# SheetMain.net
KiCad netlist of a schematic drawn in Altium Designer
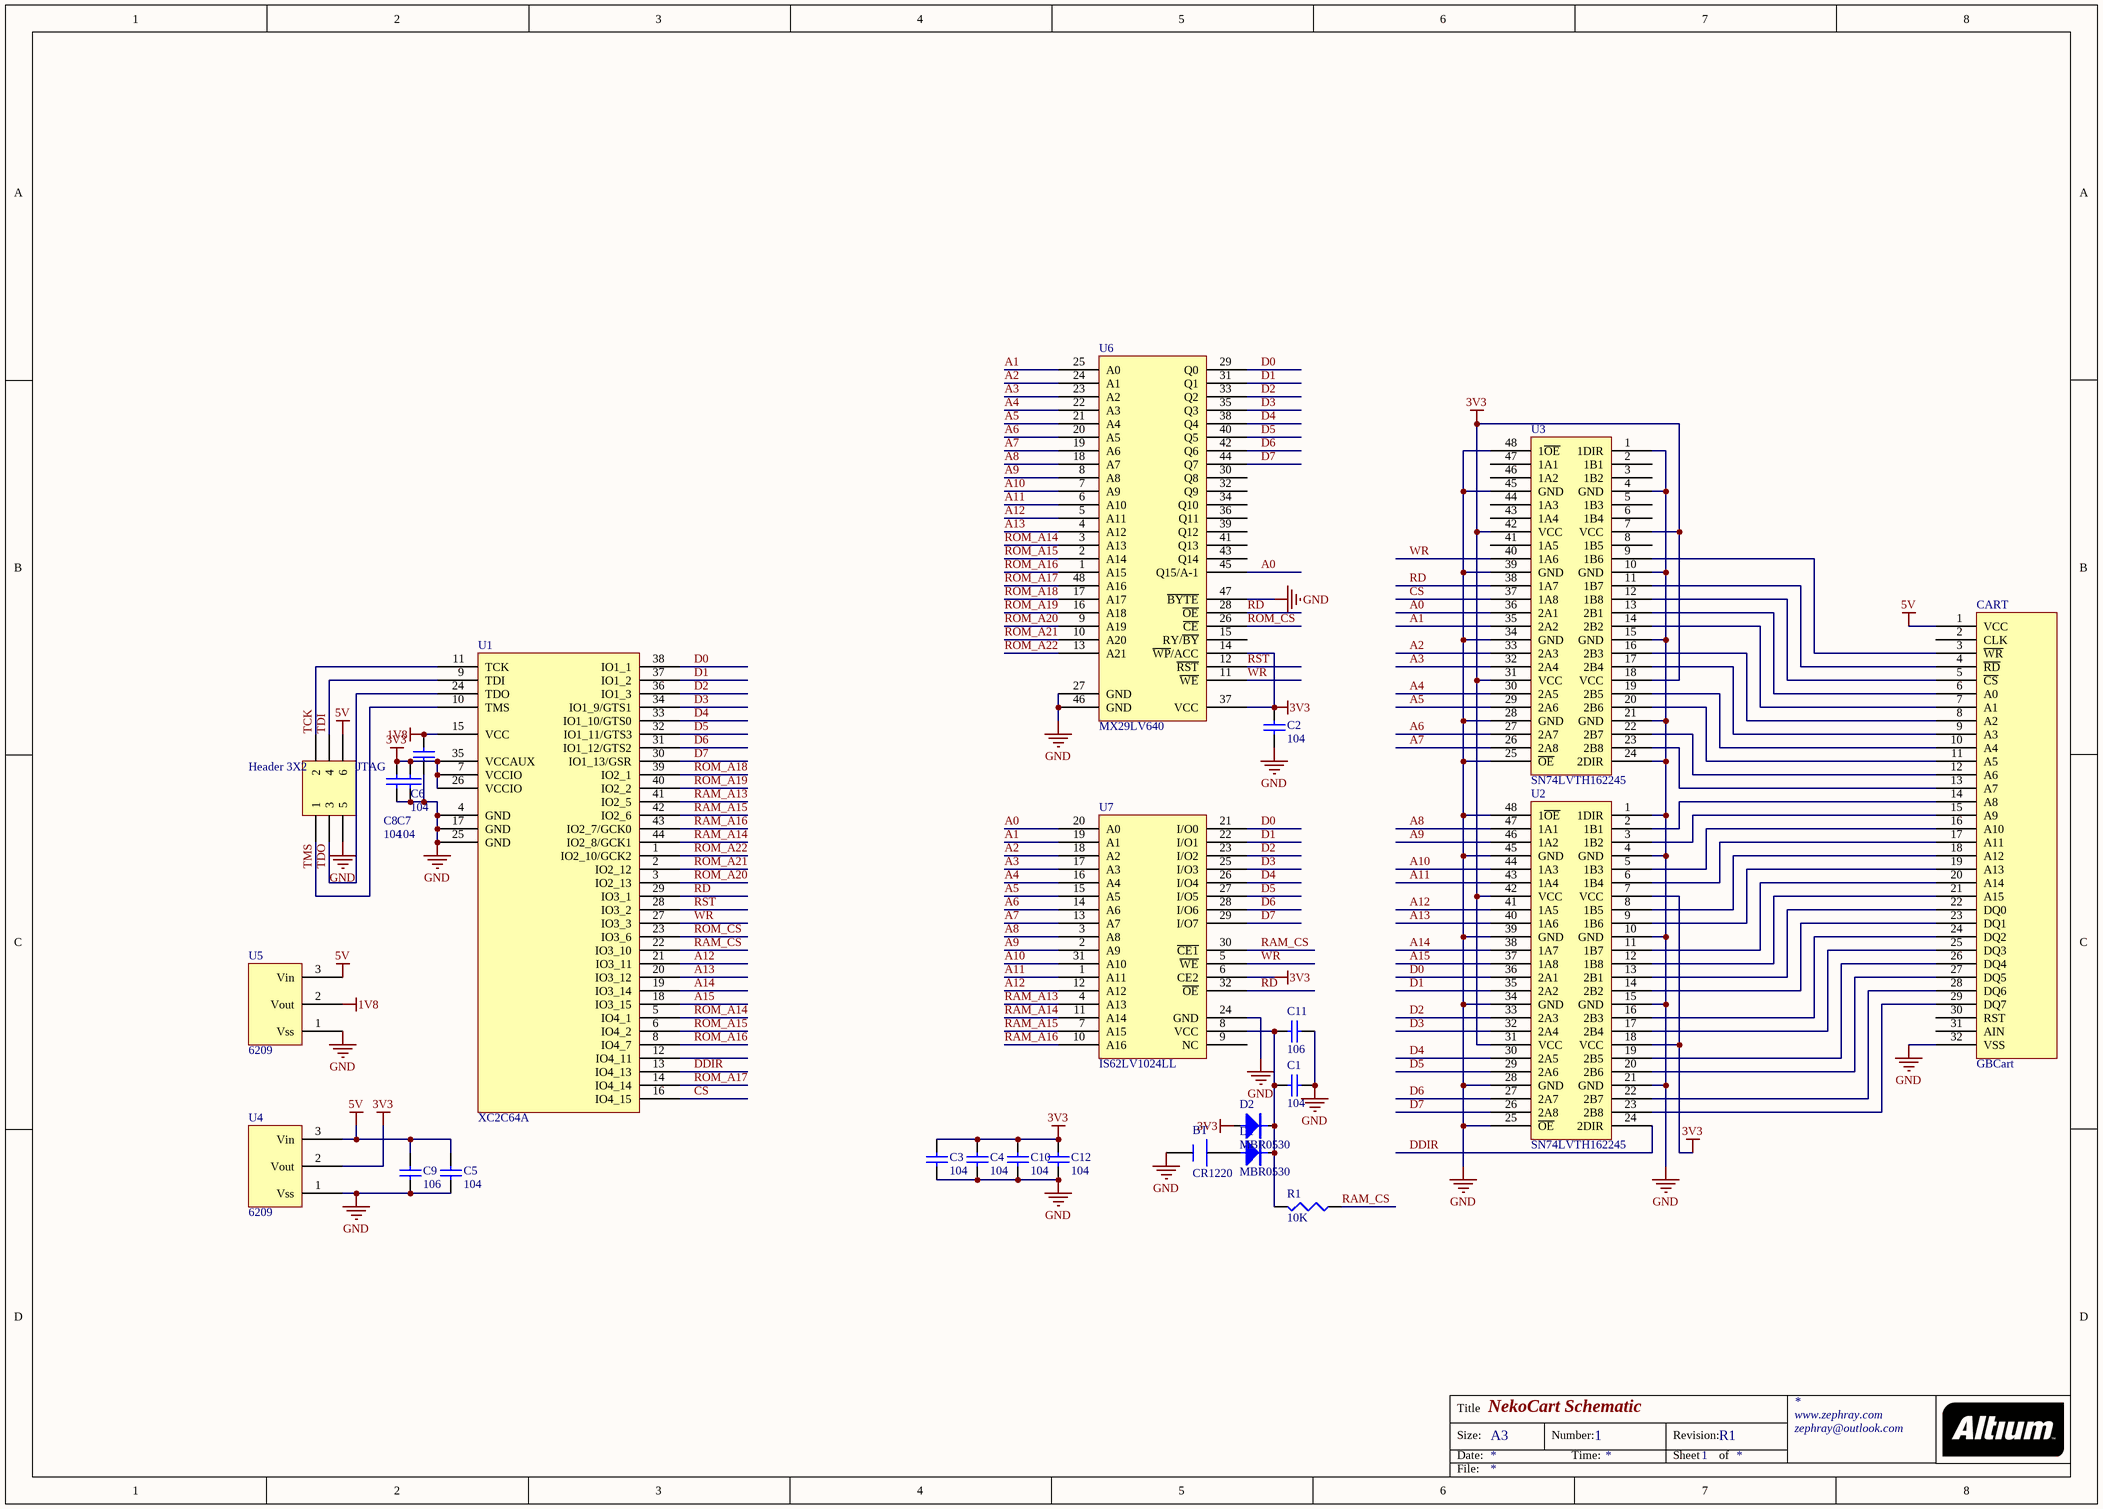
[diagram p0: SheetMain.SchDoc]

(export (version "E")
  (design (tool "Eeschema 10.0.6"))
  (components
    (comp (ref "BT")
      (value "CR1220")
      (footprint "CR1220")
      (fields (field (name "PUBLISHER") "Altium Limited"))
      (libsource (lib "Schlib1") (part "CR1220"))
    )
    (comp (ref "C1")
      (value "104")
      (footprint "1608[0603]")
      (description "Capacitor (Semiconductor SIM Model)")
      (fields (field (name "PUBLISHER") "Altium Limited"))
      (libsource (lib "Miscellaneous Devices") (part "Cap Semi"))
    )
    (comp (ref "C2")
      (value "104")
      (footprint "1608[0603]")
      (description "Capacitor (Semiconductor SIM Model)")
      (fields (field (name "PUBLISHER") "Altium Limited"))
      (libsource (lib "Miscellaneous Devices") (part "Cap Semi"))
    )
    (comp (ref "C3")
      (value "104")
      (footprint "1608[0603]")
      (description "Capacitor (Semiconductor SIM Model)")
      (fields (field (name "PUBLISHER") "Altium Limited"))
      (libsource (lib "Miscellaneous Devices") (part "Cap Semi"))
    )
    (comp (ref "C4")
      (value "104")
      (footprint "1608[0603]")
      (description "Capacitor (Semiconductor SIM Model)")
      (fields (field (name "PUBLISHER") "Altium Limited"))
      (libsource (lib "Miscellaneous Devices") (part "Cap Semi"))
    )
    (comp (ref "C5")
      (value "104")
      (footprint "1608[0603]")
      (description "Capacitor (Semiconductor SIM Model)")
      (fields (field (name "PUBLISHER") "Altium Limited"))
      (libsource (lib "Miscellaneous Devices") (part "Cap Semi"))
    )
    (comp (ref "C6")
      (value "104")
      (footprint "1608[0603]")
      (description "Capacitor (Semiconductor SIM Model)")
      (fields (field (name "PUBLISHER") "Altium Limited"))
      (libsource (lib "Miscellaneous Devices") (part "Cap Semi"))
    )
    (comp (ref "C7")
      (value "104")
      (footprint "1608[0603]")
      (description "Capacitor (Semiconductor SIM Model)")
      (fields (field (name "PUBLISHER") "Altium Limited"))
      (libsource (lib "Miscellaneous Devices") (part "Cap Semi"))
    )
    (comp (ref "C8")
      (value "104")
      (footprint "1608[0603]")
      (description "Capacitor (Semiconductor SIM Model)")
      (fields (field (name "PUBLISHER") "Altium Limited"))
      (libsource (lib "Miscellaneous Devices") (part "Cap Semi"))
    )
    (comp (ref "C9")
      (value "106")
      (footprint "C0805")
      (description "Capacitor (Semiconductor SIM Model)")
      (fields (field (name "PUBLISHER") "Altium Limited"))
      (libsource (lib "Miscellaneous Devices") (part "Cap Semi"))
    )
    (comp (ref "C10")
      (value "104")
      (footprint "1608[0603]")
      (description "Capacitor (Semiconductor SIM Model)")
      (fields (field (name "PUBLISHER") "Altium Limited"))
      (libsource (lib "Miscellaneous Devices") (part "Cap Semi"))
    )
    (comp (ref "C11")
      (value "106")
      (footprint "C0805")
      (description "Capacitor (Semiconductor SIM Model)")
      (fields (field (name "PUBLISHER") "Altium Limited"))
      (libsource (lib "Miscellaneous Devices") (part "Cap Semi"))
    )
    (comp (ref "C12")
      (value "104")
      (footprint "1608[0603]")
      (description "Capacitor (Semiconductor SIM Model)")
      (fields (field (name "PUBLISHER") "Altium Limited"))
      (libsource (lib "Miscellaneous Devices") (part "Cap Semi"))
    )
    (comp (ref "CART") (value "GBCart") (footprint "GB_CART") (libsource (lib "Schlib1") (part "GBCart")))
    (comp (ref "D1") (value "MBR0530") (footprint "0805D") (libsource (lib "Schlib1") (part "1N4148")))
    (comp (ref "D2") (value "MBR0530") (footprint "0805D") (libsource (lib "Schlib1") (part "1N4148")))
    (comp (ref "JTAG")
      (value "Header 3X2")
      (footprint "HDR2X3")
      (description "Header, 3-Pin, Dual row")
      (fields (field (name "PUBLISHER") "Altium Limited"))
      (libsource (lib "Miscellaneous Connectors") (part "Header 3X2"))
    )
    (comp (ref "R1")
      (value "10K")
      (footprint "J1-0603")
      (description "Resistor")
      (fields (field (name "PUBLISHER") "Altium Limited"))
      (libsource (lib "Miscellaneous Devices") (part "Res3"))
    )
    (comp (ref "U1") (value "XC2C64A") (footprint "44A_L") (libsource (lib "Schlib1") (part "XC2C64A")))
    (comp (ref "U2")
      (value "SN74LVTH162245")
      (footprint "TSOP48")
      (libsource (lib "Schlib1") (part "SN74LVTH162245"))
    )
    (comp (ref "U3")
      (value "SN74LVTH162245")
      (footprint "TSOP48")
      (libsource (lib "Schlib1") (part "SN74LVTH162245"))
    )
    (comp (ref "U4") (value "6209") (footprint "SOT-23") (libsource (lib "Schlib1") (part "6209")))
    (comp (ref "U5") (value "6209") (footprint "SOT-23") (libsource (lib "Schlib1") (part "6209")))
    (comp (ref "U6") (value "MX29LV640") (footprint "TSOP48L") (libsource (lib "Schlib1") (part "MX29LV640")))
    (comp (ref "U7")
      (value "IS62LV1024LL")
      (footprint "TSOP32")
      (libsource (lib "Schlib1") (part "IS62LV1024LL"))
    )
  )
  (nets
    (net (code "1") (name "/A0") (class "Default")
      (node (ref "U3") (pin "36") (pinfunction "2A1_36") (pintype "passive"))
      (node (ref "U6") (pin "45") (pinfunction "Q15/A-1_45") (pintype "passive"))
      (node (ref "U7") (pin "20") (pinfunction "A0_20") (pintype "passive"))
    )
    (net (code "2") (name "/A1") (class "Default")
      (node (ref "U3") (pin "35") (pinfunction "2A2_35") (pintype "passive"))
      (node (ref "U6") (pin "25") (pinfunction "A0_25") (pintype "passive"))
      (node (ref "U7") (pin "19") (pinfunction "A1_19") (pintype "passive"))
    )
    (net (code "3") (name "/A2") (class "Default")
      (node (ref "U3") (pin "33") (pinfunction "2A3_33") (pintype "passive"))
      (node (ref "U6") (pin "24") (pinfunction "A1_24") (pintype "passive"))
      (node (ref "U7") (pin "18") (pinfunction "A2_18") (pintype "passive"))
    )
    (net (code "4") (name "/A3") (class "Default")
      (node (ref "U3") (pin "32") (pinfunction "2A4_32") (pintype "passive"))
      (node (ref "U6") (pin "23") (pinfunction "A2_23") (pintype "passive"))
      (node (ref "U7") (pin "17") (pinfunction "A3_17") (pintype "passive"))
    )
    (net (code "5") (name "/A4") (class "Default")
      (node (ref "U3") (pin "30") (pinfunction "2A5_30") (pintype "passive"))
      (node (ref "U6") (pin "22") (pinfunction "A3_22") (pintype "passive"))
      (node (ref "U7") (pin "16") (pinfunction "A4_16") (pintype "passive"))
    )
    (net (code "6") (name "/A5") (class "Default")
      (node (ref "U3") (pin "29") (pinfunction "2A6_29") (pintype "passive"))
      (node (ref "U6") (pin "21") (pinfunction "A4_21") (pintype "passive"))
      (node (ref "U7") (pin "15") (pinfunction "A5_15") (pintype "passive"))
    )
    (net (code "7") (name "/A6") (class "Default")
      (node (ref "U3") (pin "27") (pinfunction "2A7_27") (pintype "passive"))
      (node (ref "U6") (pin "20") (pinfunction "A5_20") (pintype "passive"))
      (node (ref "U7") (pin "14") (pinfunction "A6_14") (pintype "passive"))
    )
    (net (code "8") (name "/A7") (class "Default")
      (node (ref "U3") (pin "26") (pinfunction "2A8_26") (pintype "passive"))
      (node (ref "U6") (pin "19") (pinfunction "A6_19") (pintype "passive"))
      (node (ref "U7") (pin "13") (pinfunction "A7_13") (pintype "passive"))
    )
    (net (code "9") (name "/A8") (class "Default")
      (node (ref "U2") (pin "47") (pinfunction "1A1_47") (pintype "passive"))
      (node (ref "U6") (pin "18") (pinfunction "A7_18") (pintype "passive"))
      (node (ref "U7") (pin "3") (pinfunction "A8_3") (pintype "passive"))
    )
    (net (code "10") (name "/A9") (class "Default")
      (node (ref "U2") (pin "46") (pinfunction "1A2_46") (pintype "passive"))
      (node (ref "U6") (pin "8") (pinfunction "A8_8") (pintype "passive"))
      (node (ref "U7") (pin "2") (pinfunction "A9_2") (pintype "passive"))
    )
    (net (code "11") (name "/A10") (class "Default")
      (node (ref "U2") (pin "44") (pinfunction "1A3_44") (pintype "passive"))
      (node (ref "U6") (pin "7") (pinfunction "A9_7") (pintype "passive"))
      (node (ref "U7") (pin "31") (pinfunction "A10_31") (pintype "passive"))
    )
    (net (code "12") (name "/A11") (class "Default")
      (node (ref "U2") (pin "43") (pinfunction "1A4_43") (pintype "passive"))
      (node (ref "U6") (pin "6") (pinfunction "A10_6") (pintype "passive"))
      (node (ref "U7") (pin "1") (pinfunction "A11_1") (pintype "passive"))
    )
    (net (code "13") (name "/A12") (class "Default")
      (node (ref "U1") (pin "21") (pinfunction "IO3_11_21") (pintype "passive"))
      (node (ref "U2") (pin "41") (pinfunction "1A5_41") (pintype "passive"))
      (node (ref "U6") (pin "5") (pinfunction "A11_5") (pintype "passive"))
      (node (ref "U7") (pin "12") (pinfunction "A12_12") (pintype "passive"))
    )
    (net (code "14") (name "/A13") (class "Default")
      (node (ref "U1") (pin "20") (pinfunction "IO3_12_20") (pintype "passive"))
      (node (ref "U2") (pin "40") (pinfunction "1A6_40") (pintype "passive"))
      (node (ref "U6") (pin "4") (pinfunction "A12_4") (pintype "passive"))
    )
    (net (code "15") (name "/A14") (class "Default")
      (node (ref "U1") (pin "19") (pinfunction "IO3_14_19") (pintype "passive"))
      (node (ref "U2") (pin "38") (pinfunction "1A7_38") (pintype "passive"))
    )
    (net (code "16") (name "/A15") (class "Default")
      (node (ref "U1") (pin "18") (pinfunction "IO3_15_18") (pintype "passive"))
      (node (ref "U2") (pin "37") (pinfunction "1A8_37") (pintype "passive"))
    )
    (net (code "17") (name "/CS") (class "Default")
      (node (ref "U1") (pin "16") (pinfunction "IO4_15_16") (pintype "passive"))
      (node (ref "U3") (pin "37") (pinfunction "1A8_37") (pintype "passive"))
    )
    (net (code "18") (name "/D0") (class "Default")
      (node (ref "U1") (pin "38") (pinfunction "IO1_1_38") (pintype "passive"))
      (node (ref "U2") (pin "36") (pinfunction "2A1_36") (pintype "passive"))
      (node (ref "U6") (pin "29") (pinfunction "Q0_29") (pintype "passive"))
      (node (ref "U7") (pin "21") (pinfunction "I/O0_21") (pintype "passive"))
    )
    (net (code "19") (name "/D1") (class "Default")
      (node (ref "U1") (pin "37") (pinfunction "IO1_2_37") (pintype "passive"))
      (node (ref "U2") (pin "35") (pinfunction "2A2_35") (pintype "passive"))
      (node (ref "U6") (pin "31") (pinfunction "Q1_31") (pintype "passive"))
      (node (ref "U7") (pin "22") (pinfunction "I/O1_22") (pintype "passive"))
    )
    (net (code "20") (name "/D2") (class "Default")
      (node (ref "U1") (pin "36") (pinfunction "IO1_3_36") (pintype "passive"))
      (node (ref "U2") (pin "33") (pinfunction "2A3_33") (pintype "passive"))
      (node (ref "U6") (pin "33") (pinfunction "Q2_33") (pintype "passive"))
      (node (ref "U7") (pin "23") (pinfunction "I/O2_23") (pintype "passive"))
    )
    (net (code "21") (name "/D3") (class "Default")
      (node (ref "U1") (pin "34") (pinfunction "IO1_9/GTS1_34") (pintype "passive"))
      (node (ref "U2") (pin "32") (pinfunction "2A4_32") (pintype "passive"))
      (node (ref "U6") (pin "35") (pinfunction "Q3_35") (pintype "passive"))
      (node (ref "U7") (pin "25") (pinfunction "I/O3_25") (pintype "passive"))
    )
    (net (code "22") (name "/D4") (class "Default")
      (node (ref "U1") (pin "33") (pinfunction "IO1_10/GTS0_33") (pintype "passive"))
      (node (ref "U2") (pin "30") (pinfunction "2A5_30") (pintype "passive"))
      (node (ref "U6") (pin "38") (pinfunction "Q4_38") (pintype "passive"))
      (node (ref "U7") (pin "26") (pinfunction "I/O4_26") (pintype "passive"))
    )
    (net (code "23") (name "/D5") (class "Default")
      (node (ref "U1") (pin "32") (pinfunction "IO1_11/GTS3_32") (pintype "passive"))
      (node (ref "U2") (pin "29") (pinfunction "2A6_29") (pintype "passive"))
      (node (ref "U6") (pin "40") (pinfunction "Q5_40") (pintype "passive"))
      (node (ref "U7") (pin "27") (pinfunction "I/O5_27") (pintype "passive"))
    )
    (net (code "24") (name "/D6") (class "Default")
      (node (ref "U1") (pin "31") (pinfunction "IO1_12/GTS2_31") (pintype "passive"))
      (node (ref "U2") (pin "27") (pinfunction "2A7_27") (pintype "passive"))
      (node (ref "U6") (pin "42") (pinfunction "Q6_42") (pintype "passive"))
      (node (ref "U7") (pin "28") (pinfunction "I/O6_28") (pintype "passive"))
    )
    (net (code "25") (name "/D7") (class "Default")
      (node (ref "U1") (pin "30") (pinfunction "IO1_13/GSR_30") (pintype "passive"))
      (node (ref "U2") (pin "26") (pinfunction "2A8_26") (pintype "passive"))
      (node (ref "U6") (pin "44") (pinfunction "Q7_44") (pintype "passive"))
      (node (ref "U7") (pin "29") (pinfunction "I/O7_29") (pintype "passive"))
    )
    (net (code "26") (name "/DDIR") (class "Default")
      (node (ref "U1") (pin "13") (pinfunction "IO4_13_13") (pintype "passive"))
      (node (ref "U2") (pin "24") (pinfunction "2DIR_24") (pintype "passive"))
    )
    (net (code "27") (name "/RAM_A13") (class "Default")
      (node (ref "U1") (pin "41") (pinfunction "IO2_5_41") (pintype "passive"))
      (node (ref "U7") (pin "4") (pinfunction "A13_4") (pintype "passive"))
    )
    (net (code "28") (name "/RAM_A14") (class "Default")
      (node (ref "U1") (pin "44") (pinfunction "IO2_8/GCK1_44") (pintype "passive"))
      (node (ref "U7") (pin "11") (pinfunction "A14_11") (pintype "passive"))
    )
    (net (code "29") (name "/RAM_A15") (class "Default")
      (node (ref "U1") (pin "42") (pinfunction "IO2_6_42") (pintype "passive"))
      (node (ref "U7") (pin "7") (pinfunction "A15_7") (pintype "passive"))
    )
    (net (code "30") (name "/RAM_A16") (class "Default")
      (node (ref "U1") (pin "43") (pinfunction "IO2_7/GCK0_43") (pintype "passive"))
      (node (ref "U7") (pin "10") (pinfunction "A16_10") (pintype "passive"))
    )
    (net (code "31") (name "/RAM_CS") (class "Default")
      (node (ref "R1") (pin "1") (pinfunction "1_1") (pintype "passive"))
      (node (ref "U1") (pin "22") (pinfunction "IO3_10_22") (pintype "passive"))
      (node (ref "U7") (pin "30") (pinfunction "~{CE1}_30") (pintype "passive"))
    )
    (net (code "32") (name "/RD") (class "Default")
      (node (ref "U1") (pin "29") (pinfunction "IO3_1_29") (pintype "passive"))
      (node (ref "U3") (pin "38") (pinfunction "1A7_38") (pintype "passive"))
      (node (ref "U6") (pin "28") (pinfunction "~{OE}_28") (pintype "passive"))
      (node (ref "U7") (pin "32") (pinfunction "~{OE}_32") (pintype "passive"))
    )
    (net (code "33") (name "/ROM_A14") (class "Default")
      (node (ref "U1") (pin "5") (pinfunction "IO4_1_5") (pintype "passive"))
      (node (ref "U6") (pin "3") (pinfunction "A13_3") (pintype "passive"))
    )
    (net (code "34") (name "/ROM_A15") (class "Default")
      (node (ref "U1") (pin "6") (pinfunction "IO4_2_6") (pintype "passive"))
      (node (ref "U6") (pin "2") (pinfunction "A14_2") (pintype "passive"))
    )
    (net (code "35") (name "/ROM_A16") (class "Default")
      (node (ref "U1") (pin "8") (pinfunction "IO4_7_8") (pintype "passive"))
      (node (ref "U6") (pin "1") (pinfunction "A15_1") (pintype "passive"))
    )
    (net (code "36") (name "/ROM_A17") (class "Default")
      (node (ref "U1") (pin "14") (pinfunction "IO4_14_14") (pintype "passive"))
      (node (ref "U6") (pin "48") (pinfunction "A16_48") (pintype "passive"))
    )
    (net (code "37") (name "/ROM_A18") (class "Default")
      (node (ref "U1") (pin "39") (pinfunction "IO2_1_39") (pintype "passive"))
      (node (ref "U6") (pin "17") (pinfunction "A17_17") (pintype "passive"))
    )
    (net (code "38") (name "/ROM_A19") (class "Default")
      (node (ref "U1") (pin "40") (pinfunction "IO2_2_40") (pintype "passive"))
      (node (ref "U6") (pin "16") (pinfunction "A18_16") (pintype "passive"))
    )
    (net (code "39") (name "/ROM_A20") (class "Default")
      (node (ref "U1") (pin "3") (pinfunction "IO2_13_3") (pintype "passive"))
      (node (ref "U6") (pin "9") (pinfunction "A19_9") (pintype "passive"))
    )
    (net (code "40") (name "/ROM_A21") (class "Default")
      (node (ref "U1") (pin "2") (pinfunction "IO2_12_2") (pintype "passive"))
      (node (ref "U6") (pin "10") (pinfunction "A20_10") (pintype "passive"))
    )
    (net (code "41") (name "/ROM_A22") (class "Default")
      (node (ref "U1") (pin "1") (pinfunction "IO2_10/GCK2_1") (pintype "passive"))
      (node (ref "U6") (pin "13") (pinfunction "A21_13") (pintype "passive"))
    )
    (net (code "42") (name "/ROM_CS") (class "Default")
      (node (ref "U1") (pin "23") (pinfunction "IO3_6_23") (pintype "passive"))
      (node (ref "U6") (pin "26") (pinfunction "~{CE}_26") (pintype "passive"))
    )
    (net (code "43") (name "/RST") (class "Default")
      (node (ref "U1") (pin "28") (pinfunction "IO3_2_28") (pintype "passive"))
      (node (ref "U6") (pin "12") (pinfunction "~{RST}_12") (pintype "passive"))
    )
    (net (code "44") (name "/TCK") (class "Default")
      (node (ref "JTAG") (pin "2") (pinfunction "2_2") (pintype "passive"))
      (node (ref "U1") (pin "11") (pinfunction "TCK_11") (pintype "passive"))
    )
    (net (code "45") (name "/TDI") (class "Default")
      (node (ref "JTAG") (pin "4") (pinfunction "4_4") (pintype "passive"))
      (node (ref "U1") (pin "9") (pinfunction "TDI_9") (pintype "passive"))
    )
    (net (code "46") (name "/TDO") (class "Default")
      (node (ref "JTAG") (pin "3") (pinfunction "3_3") (pintype "passive"))
      (node (ref "U1") (pin "24") (pinfunction "TDO_24") (pintype "passive"))
    )
    (net (code "47") (name "/TMS") (class "Default")
      (node (ref "JTAG") (pin "1") (pinfunction "1_1") (pintype "passive"))
      (node (ref "U1") (pin "10") (pinfunction "TMS_10") (pintype "passive"))
    )
    (net (code "48") (name "/WR") (class "Default")
      (node (ref "U1") (pin "27") (pinfunction "IO3_3_27") (pintype "passive"))
      (node (ref "U3") (pin "40") (pinfunction "1A6_40") (pintype "passive"))
      (node (ref "U6") (pin "11") (pinfunction "~{WE}_11") (pintype "passive"))
      (node (ref "U7") (pin "5") (pinfunction "~{WE}_5") (pintype "passive"))
    )
    (net (code "49") (name "1V8") (class "Default")
      (node (ref "C6") (pin "2") (pinfunction "2_2") (pintype "passive"))
      (node (ref "U1") (pin "15") (pinfunction "VCC_15") (pintype "passive"))
      (node (ref "U5") (pin "2") (pinfunction "Vout_2") (pintype "passive"))
    )
    (net (code "50") (name "3V3") (class "Default")
      (node (ref "C10") (pin "1") (pinfunction "1_1") (pintype "passive"))
      (node (ref "C12") (pin "2") (pinfunction "2_2") (pintype "passive"))
      (node (ref "C2") (pin "2") (pinfunction "2_2") (pintype "passive"))
      (node (ref "C3") (pin "2") (pinfunction "2_2") (pintype "passive"))
      (node (ref "C4") (pin "2") (pinfunction "2_2") (pintype "passive"))
      (node (ref "C7") (pin "2") (pinfunction "2_2") (pintype "passive"))
      (node (ref "C8") (pin "2") (pinfunction "2_2") (pintype "passive"))
      (node (ref "D2") (pin "A") (pinfunction "1_A") (pintype "passive"))
      (node (ref "U1") (pin "26") (pinfunction "VCCIO_26") (pintype "passive"))
      (node (ref "U1") (pin "35") (pinfunction "VCCAUX_35") (pintype "passive"))
      (node (ref "U1") (pin "7") (pinfunction "VCCIO_7") (pintype "passive"))
      (node (ref "U2") (pin "18") (pinfunction "VCC_18") (pintype "passive"))
      (node (ref "U2") (pin "31") (pinfunction "VCC_31") (pintype "passive"))
      (node (ref "U2") (pin "42") (pinfunction "VCC_42") (pintype "passive"))
      (node (ref "U2") (pin "7") (pinfunction "VCC_7") (pintype "passive"))
      (node (ref "U3") (pin "18") (pinfunction "VCC_18") (pintype "passive"))
      (node (ref "U3") (pin "31") (pinfunction "VCC_31") (pintype "passive"))
      (node (ref "U3") (pin "42") (pinfunction "VCC_42") (pintype "passive"))
      (node (ref "U3") (pin "7") (pinfunction "VCC_7") (pintype "passive"))
      (node (ref "U4") (pin "2") (pinfunction "Vout_2") (pintype "passive"))
      (node (ref "U6") (pin "14") (pinfunction "~{WP}/ACC_14") (pintype "passive"))
      (node (ref "U6") (pin "37") (pinfunction "VCC_37") (pintype "passive"))
      (node (ref "U7") (pin "6") (pinfunction "CE2_6") (pintype "passive"))
    )
    (net (code "51") (name "5V") (class "Default")
      (node (ref "C5") (pin "2") (pinfunction "2_2") (pintype "passive"))
      (node (ref "C9") (pin "2") (pinfunction "2_2") (pintype "passive"))
      (node (ref "CART") (pin "1") (pinfunction "VCC_1") (pintype "passive"))
      (node (ref "JTAG") (pin "6") (pinfunction "6_6") (pintype "passive"))
      (node (ref "U4") (pin "3") (pinfunction "Vin_3") (pintype "passive"))
      (node (ref "U5") (pin "3") (pinfunction "Vin_3") (pintype "passive"))
    )
    (net (code "52") (name "GND") (class "Default")
      (node (ref "BT") (pin "2") (pinfunction "-_2") (pintype "passive"))
      (node (ref "C1") (pin "1") (pinfunction "1_1") (pintype "passive"))
      (node (ref "C10") (pin "2") (pinfunction "2_2") (pintype "passive"))
      (node (ref "C11") (pin "1") (pinfunction "1_1") (pintype "passive"))
      (node (ref "C12") (pin "1") (pinfunction "1_1") (pintype "passive"))
      (node (ref "C2") (pin "1") (pinfunction "1_1") (pintype "passive"))
      (node (ref "C3") (pin "1") (pinfunction "1_1") (pintype "passive"))
      (node (ref "C4") (pin "1") (pinfunction "1_1") (pintype "passive"))
      (node (ref "C5") (pin "1") (pinfunction "1_1") (pintype "passive"))
      (node (ref "C6") (pin "1") (pinfunction "1_1") (pintype "passive"))
      (node (ref "C7") (pin "1") (pinfunction "1_1") (pintype "passive"))
      (node (ref "C8") (pin "1") (pinfunction "1_1") (pintype "passive"))
      (node (ref "C9") (pin "1") (pinfunction "1_1") (pintype "passive"))
      (node (ref "CART") (pin "32") (pinfunction "VSS_32") (pintype "passive"))
      (node (ref "JTAG") (pin "5") (pinfunction "5_5") (pintype "passive"))
      (node (ref "U1") (pin "17") (pinfunction "GND_17") (pintype "passive"))
      (node (ref "U1") (pin "25") (pinfunction "GND_25") (pintype "passive"))
      (node (ref "U1") (pin "4") (pinfunction "GND_4") (pintype "passive"))
      (node (ref "U2") (pin "1") (pinfunction "1DIR_1") (pintype "passive"))
      (node (ref "U2") (pin "10") (pinfunction "GND_10") (pintype "passive"))
      (node (ref "U2") (pin "15") (pinfunction "GND_15") (pintype "passive"))
      (node (ref "U2") (pin "21") (pinfunction "GND_21") (pintype "passive"))
      (node (ref "U2") (pin "25") (pinfunction "~{OE}_25") (pintype "passive"))
      (node (ref "U2") (pin "28") (pinfunction "GND_28") (pintype "passive"))
      (node (ref "U2") (pin "34") (pinfunction "GND_34") (pintype "passive"))
      (node (ref "U2") (pin "39") (pinfunction "GND_39") (pintype "passive"))
      (node (ref "U2") (pin "4") (pinfunction "GND_4") (pintype "passive"))
      (node (ref "U2") (pin "45") (pinfunction "GND_45") (pintype "passive"))
      (node (ref "U2") (pin "48") (pinfunction "1~{OE}_48") (pintype "passive"))
      (node (ref "U3") (pin "1") (pinfunction "1DIR_1") (pintype "passive"))
      (node (ref "U3") (pin "10") (pinfunction "GND_10") (pintype "passive"))
      (node (ref "U3") (pin "15") (pinfunction "GND_15") (pintype "passive"))
      (node (ref "U3") (pin "21") (pinfunction "GND_21") (pintype "passive"))
      (node (ref "U3") (pin "24") (pinfunction "2DIR_24") (pintype "passive"))
      (node (ref "U3") (pin "25") (pinfunction "~{OE}_25") (pintype "passive"))
      (node (ref "U3") (pin "28") (pinfunction "GND_28") (pintype "passive"))
      (node (ref "U3") (pin "34") (pinfunction "GND_34") (pintype "passive"))
      (node (ref "U3") (pin "39") (pinfunction "GND_39") (pintype "passive"))
      (node (ref "U3") (pin "4") (pinfunction "GND_4") (pintype "passive"))
      (node (ref "U3") (pin "45") (pinfunction "GND_45") (pintype "passive"))
      (node (ref "U3") (pin "48") (pinfunction "1~{OE}_48") (pintype "passive"))
      (node (ref "U4") (pin "1") (pinfunction "Vss_1") (pintype "passive"))
      (node (ref "U5") (pin "1") (pinfunction "Vss_1") (pintype "passive"))
      (node (ref "U6") (pin "27") (pinfunction "GND_27") (pintype "passive"))
      (node (ref "U6") (pin "46") (pinfunction "GND_46") (pintype "passive"))
      (node (ref "U6") (pin "47") (pinfunction "~{BYTE}_47") (pintype "passive"))
      (node (ref "U7") (pin "24") (pinfunction "GND_24") (pintype "passive"))
    )
    (net (code "53") (name "Net-(BT-+)") (class "Default")
      (node (ref "BT") (pin "1") (pinfunction "+_1") (pintype "passive"))
      (node (ref "D1") (pin "A") (pinfunction "1_A") (pintype "passive"))
    )
    (net (code "54") (name "Net-(CART-A0)") (class "Default")
      (node (ref "CART") (pin "6") (pinfunction "A0_6") (pintype "passive"))
      (node (ref "U3") (pin "13") (pinfunction "2B1_13") (pintype "passive"))
    )
    (net (code "55") (name "Net-(CART-A1)") (class "Default")
      (node (ref "CART") (pin "7") (pinfunction "A1_7") (pintype "passive"))
      (node (ref "U3") (pin "14") (pinfunction "2B2_14") (pintype "passive"))
    )
    (net (code "56") (name "Net-(CART-A2)") (class "Default")
      (node (ref "CART") (pin "8") (pinfunction "A2_8") (pintype "passive"))
      (node (ref "U3") (pin "16") (pinfunction "2B3_16") (pintype "passive"))
    )
    (net (code "57") (name "Net-(CART-A3)") (class "Default")
      (node (ref "CART") (pin "9") (pinfunction "A3_9") (pintype "passive"))
      (node (ref "U3") (pin "17") (pinfunction "2B4_17") (pintype "passive"))
    )
    (net (code "58") (name "Net-(CART-A4)") (class "Default")
      (node (ref "CART") (pin "10") (pinfunction "A4_10") (pintype "passive"))
      (node (ref "U3") (pin "19") (pinfunction "2B5_19") (pintype "passive"))
    )
    (net (code "59") (name "Net-(CART-A5)") (class "Default")
      (node (ref "CART") (pin "11") (pinfunction "A5_11") (pintype "passive"))
      (node (ref "U3") (pin "20") (pinfunction "2B6_20") (pintype "passive"))
    )
    (net (code "60") (name "Net-(CART-A6)") (class "Default")
      (node (ref "CART") (pin "12") (pinfunction "A6_12") (pintype "passive"))
      (node (ref "U3") (pin "22") (pinfunction "2B7_22") (pintype "passive"))
    )
    (net (code "61") (name "Net-(CART-A7)") (class "Default")
      (node (ref "CART") (pin "13") (pinfunction "A7_13") (pintype "passive"))
      (node (ref "U3") (pin "23") (pinfunction "2B8_23") (pintype "passive"))
    )
    (net (code "62") (name "Net-(CART-A8)") (class "Default")
      (node (ref "CART") (pin "14") (pinfunction "A8_14") (pintype "passive"))
      (node (ref "U2") (pin "2") (pinfunction "1B1_2") (pintype "passive"))
    )
    (net (code "63") (name "Net-(CART-A9)") (class "Default")
      (node (ref "CART") (pin "15") (pinfunction "A9_15") (pintype "passive"))
      (node (ref "U2") (pin "3") (pinfunction "1B2_3") (pintype "passive"))
    )
    (net (code "64") (name "Net-(CART-A10)") (class "Default")
      (node (ref "CART") (pin "16") (pinfunction "A10_16") (pintype "passive"))
      (node (ref "U2") (pin "5") (pinfunction "1B3_5") (pintype "passive"))
    )
    (net (code "65") (name "Net-(CART-A11)") (class "Default")
      (node (ref "CART") (pin "17") (pinfunction "A11_17") (pintype "passive"))
      (node (ref "U2") (pin "6") (pinfunction "1B4_6") (pintype "passive"))
    )
    (net (code "66") (name "Net-(CART-A12)") (class "Default")
      (node (ref "CART") (pin "18") (pinfunction "A12_18") (pintype "passive"))
      (node (ref "U2") (pin "8") (pinfunction "1B5_8") (pintype "passive"))
    )
    (net (code "67") (name "Net-(CART-A13)") (class "Default")
      (node (ref "CART") (pin "19") (pinfunction "A13_19") (pintype "passive"))
      (node (ref "U2") (pin "9") (pinfunction "1B6_9") (pintype "passive"))
    )
    (net (code "68") (name "Net-(CART-A14)") (class "Default")
      (node (ref "CART") (pin "20") (pinfunction "A14_20") (pintype "passive"))
      (node (ref "U2") (pin "11") (pinfunction "1B7_11") (pintype "passive"))
    )
    (net (code "69") (name "Net-(CART-A15)") (class "Default")
      (node (ref "CART") (pin "21") (pinfunction "A15_21") (pintype "passive"))
      (node (ref "U2") (pin "12") (pinfunction "1B8_12") (pintype "passive"))
    )
    (net (code "70") (name "Net-(CART-DQ0)") (class "Default")
      (node (ref "CART") (pin "22") (pinfunction "DQ0_22") (pintype "passive"))
      (node (ref "U2") (pin "13") (pinfunction "2B1_13") (pintype "passive"))
    )
    (net (code "71") (name "Net-(CART-DQ1)") (class "Default")
      (node (ref "CART") (pin "23") (pinfunction "DQ1_23") (pintype "passive"))
      (node (ref "U2") (pin "14") (pinfunction "2B2_14") (pintype "passive"))
    )
    (net (code "72") (name "Net-(CART-DQ2)") (class "Default")
      (node (ref "CART") (pin "24") (pinfunction "DQ2_24") (pintype "passive"))
      (node (ref "U2") (pin "16") (pinfunction "2B3_16") (pintype "passive"))
    )
    (net (code "73") (name "Net-(CART-DQ3)") (class "Default")
      (node (ref "CART") (pin "25") (pinfunction "DQ3_25") (pintype "passive"))
      (node (ref "U2") (pin "17") (pinfunction "2B4_17") (pintype "passive"))
    )
    (net (code "74") (name "Net-(CART-DQ4)") (class "Default")
      (node (ref "CART") (pin "26") (pinfunction "DQ4_26") (pintype "passive"))
      (node (ref "U2") (pin "19") (pinfunction "2B5_19") (pintype "passive"))
    )
    (net (code "75") (name "Net-(CART-DQ5)") (class "Default")
      (node (ref "CART") (pin "27") (pinfunction "DQ5_27") (pintype "passive"))
      (node (ref "U2") (pin "20") (pinfunction "2B6_20") (pintype "passive"))
    )
    (net (code "76") (name "Net-(CART-DQ6)") (class "Default")
      (node (ref "CART") (pin "28") (pinfunction "DQ6_28") (pintype "passive"))
      (node (ref "U2") (pin "22") (pinfunction "2B7_22") (pintype "passive"))
    )
    (net (code "77") (name "Net-(CART-DQ7)") (class "Default")
      (node (ref "CART") (pin "29") (pinfunction "DQ7_29") (pintype "passive"))
      (node (ref "U2") (pin "23") (pinfunction "2B8_23") (pintype "passive"))
    )
    (net (code "78") (name "Net-(CART-~{CS})") (class "Default")
      (node (ref "CART") (pin "5") (pinfunction "~{CS}_5") (pintype "passive"))
      (node (ref "U3") (pin "12") (pinfunction "1B8_12") (pintype "passive"))
    )
    (net (code "79") (name "Net-(CART-~{RD})") (class "Default")
      (node (ref "CART") (pin "4") (pinfunction "~{RD}_4") (pintype "passive"))
      (node (ref "U3") (pin "11") (pinfunction "1B7_11") (pintype "passive"))
    )
    (net (code "80") (name "Net-(CART-~{WR})") (class "Default")
      (node (ref "CART") (pin "3") (pinfunction "~{WR}_3") (pintype "passive"))
      (node (ref "U3") (pin "9") (pinfunction "1B6_9") (pintype "passive"))
    )
    (net (code "81") (name "Net-(D1-2)") (class "Default")
      (node (ref "C1") (pin "2") (pinfunction "2_2") (pintype "passive"))
      (node (ref "C11") (pin "2") (pinfunction "2_2") (pintype "passive"))
      (node (ref "D1") (pin "K") (pinfunction "2_K") (pintype "passive"))
      (node (ref "D2") (pin "K") (pinfunction "2_K") (pintype "passive"))
      (node (ref "R1") (pin "2") (pinfunction "2_2") (pintype "passive"))
      (node (ref "U7") (pin "8") (pinfunction "VCC_8") (pintype "passive"))
    )
    (net (code "82") (name "unconnected-(CART-AIN-Pad31)") (class "Default")
      (node (ref "CART") (pin "31") (pinfunction "AIN_31") (pintype "passive"))
    )
    (net (code "83") (name "unconnected-(CART-CLK-Pad2)") (class "Default")
      (node (ref "CART") (pin "2") (pinfunction "CLK_2") (pintype "passive"))
    )
    (net (code "84") (name "unconnected-(CART-RST-Pad30)") (class "Default")
      (node (ref "CART") (pin "30") (pinfunction "RST_30") (pintype "passive"))
    )
    (net (code "85") (name "unconnected-(U1-IO4_11-Pad12)") (class "Default")
      (node (ref "U1") (pin "12") (pinfunction "IO4_11_12") (pintype "passive"))
    )
    (net (code "86") (name "unconnected-(U3-1A1-Pad47)") (class "Default")
      (node (ref "U3") (pin "47") (pinfunction "1A1_47") (pintype "passive"))
    )
    (net (code "87") (name "unconnected-(U3-1A2-Pad46)") (class "Default")
      (node (ref "U3") (pin "46") (pinfunction "1A2_46") (pintype "passive"))
    )
    (net (code "88") (name "unconnected-(U3-1A3-Pad44)") (class "Default")
      (node (ref "U3") (pin "44") (pinfunction "1A3_44") (pintype "passive"))
    )
    (net (code "89") (name "unconnected-(U3-1A4-Pad43)") (class "Default")
      (node (ref "U3") (pin "43") (pinfunction "1A4_43") (pintype "passive"))
    )
    (net (code "90") (name "unconnected-(U3-1A5-Pad41)") (class "Default")
      (node (ref "U3") (pin "41") (pinfunction "1A5_41") (pintype "passive"))
    )
    (net (code "91") (name "unconnected-(U3-1B1-Pad2)") (class "Default")
      (node (ref "U3") (pin "2") (pinfunction "1B1_2") (pintype "passive"))
    )
    (net (code "92") (name "unconnected-(U3-1B2-Pad3)") (class "Default")
      (node (ref "U3") (pin "3") (pinfunction "1B2_3") (pintype "passive"))
    )
    (net (code "93") (name "unconnected-(U3-1B3-Pad5)") (class "Default")
      (node (ref "U3") (pin "5") (pinfunction "1B3_5") (pintype "passive"))
    )
    (net (code "94") (name "unconnected-(U3-1B4-Pad6)") (class "Default")
      (node (ref "U3") (pin "6") (pinfunction "1B4_6") (pintype "passive"))
    )
    (net (code "95") (name "unconnected-(U3-1B5-Pad8)") (class "Default")
      (node (ref "U3") (pin "8") (pinfunction "1B5_8") (pintype "passive"))
    )
    (net (code "96") (name "unconnected-(U6-Q8-Pad30)") (class "Default")
      (node (ref "U6") (pin "30") (pinfunction "Q8_30") (pintype "passive"))
    )
    (net (code "97") (name "unconnected-(U6-Q9-Pad32)") (class "Default")
      (node (ref "U6") (pin "32") (pinfunction "Q9_32") (pintype "passive"))
    )
    (net (code "98") (name "unconnected-(U6-Q10-Pad34)") (class "Default")
      (node (ref "U6") (pin "34") (pinfunction "Q10_34") (pintype "passive"))
    )
    (net (code "99") (name "unconnected-(U6-Q11-Pad36)") (class "Default")
      (node (ref "U6") (pin "36") (pinfunction "Q11_36") (pintype "passive"))
    )
    (net (code "100") (name "unconnected-(U6-Q12-Pad39)") (class "Default")
      (node (ref "U6") (pin "39") (pinfunction "Q12_39") (pintype "passive"))
    )
    (net (code "101") (name "unconnected-(U6-Q13-Pad41)") (class "Default")
      (node (ref "U6") (pin "41") (pinfunction "Q13_41") (pintype "passive"))
    )
    (net (code "102") (name "unconnected-(U6-Q14-Pad43)") (class "Default")
      (node (ref "U6") (pin "43") (pinfunction "Q14_43") (pintype "passive"))
    )
    (net (code "103") (name "unconnected-(U6-RY{slash}~{BY}-Pad15)") (class "Default")
      (node (ref "U6") (pin "15") (pinfunction "RY/~{BY}_15") (pintype "passive"))
    )
    (net (code "104") (name "unconnected-(U7-NC-Pad9)") (class "Default")
      (node (ref "U7") (pin "9") (pinfunction "NC_9") (pintype "passive"))
    )
  )
)
